# lazurite_rev3.net
KiCad netlist of a schematic drawn in EAGLE
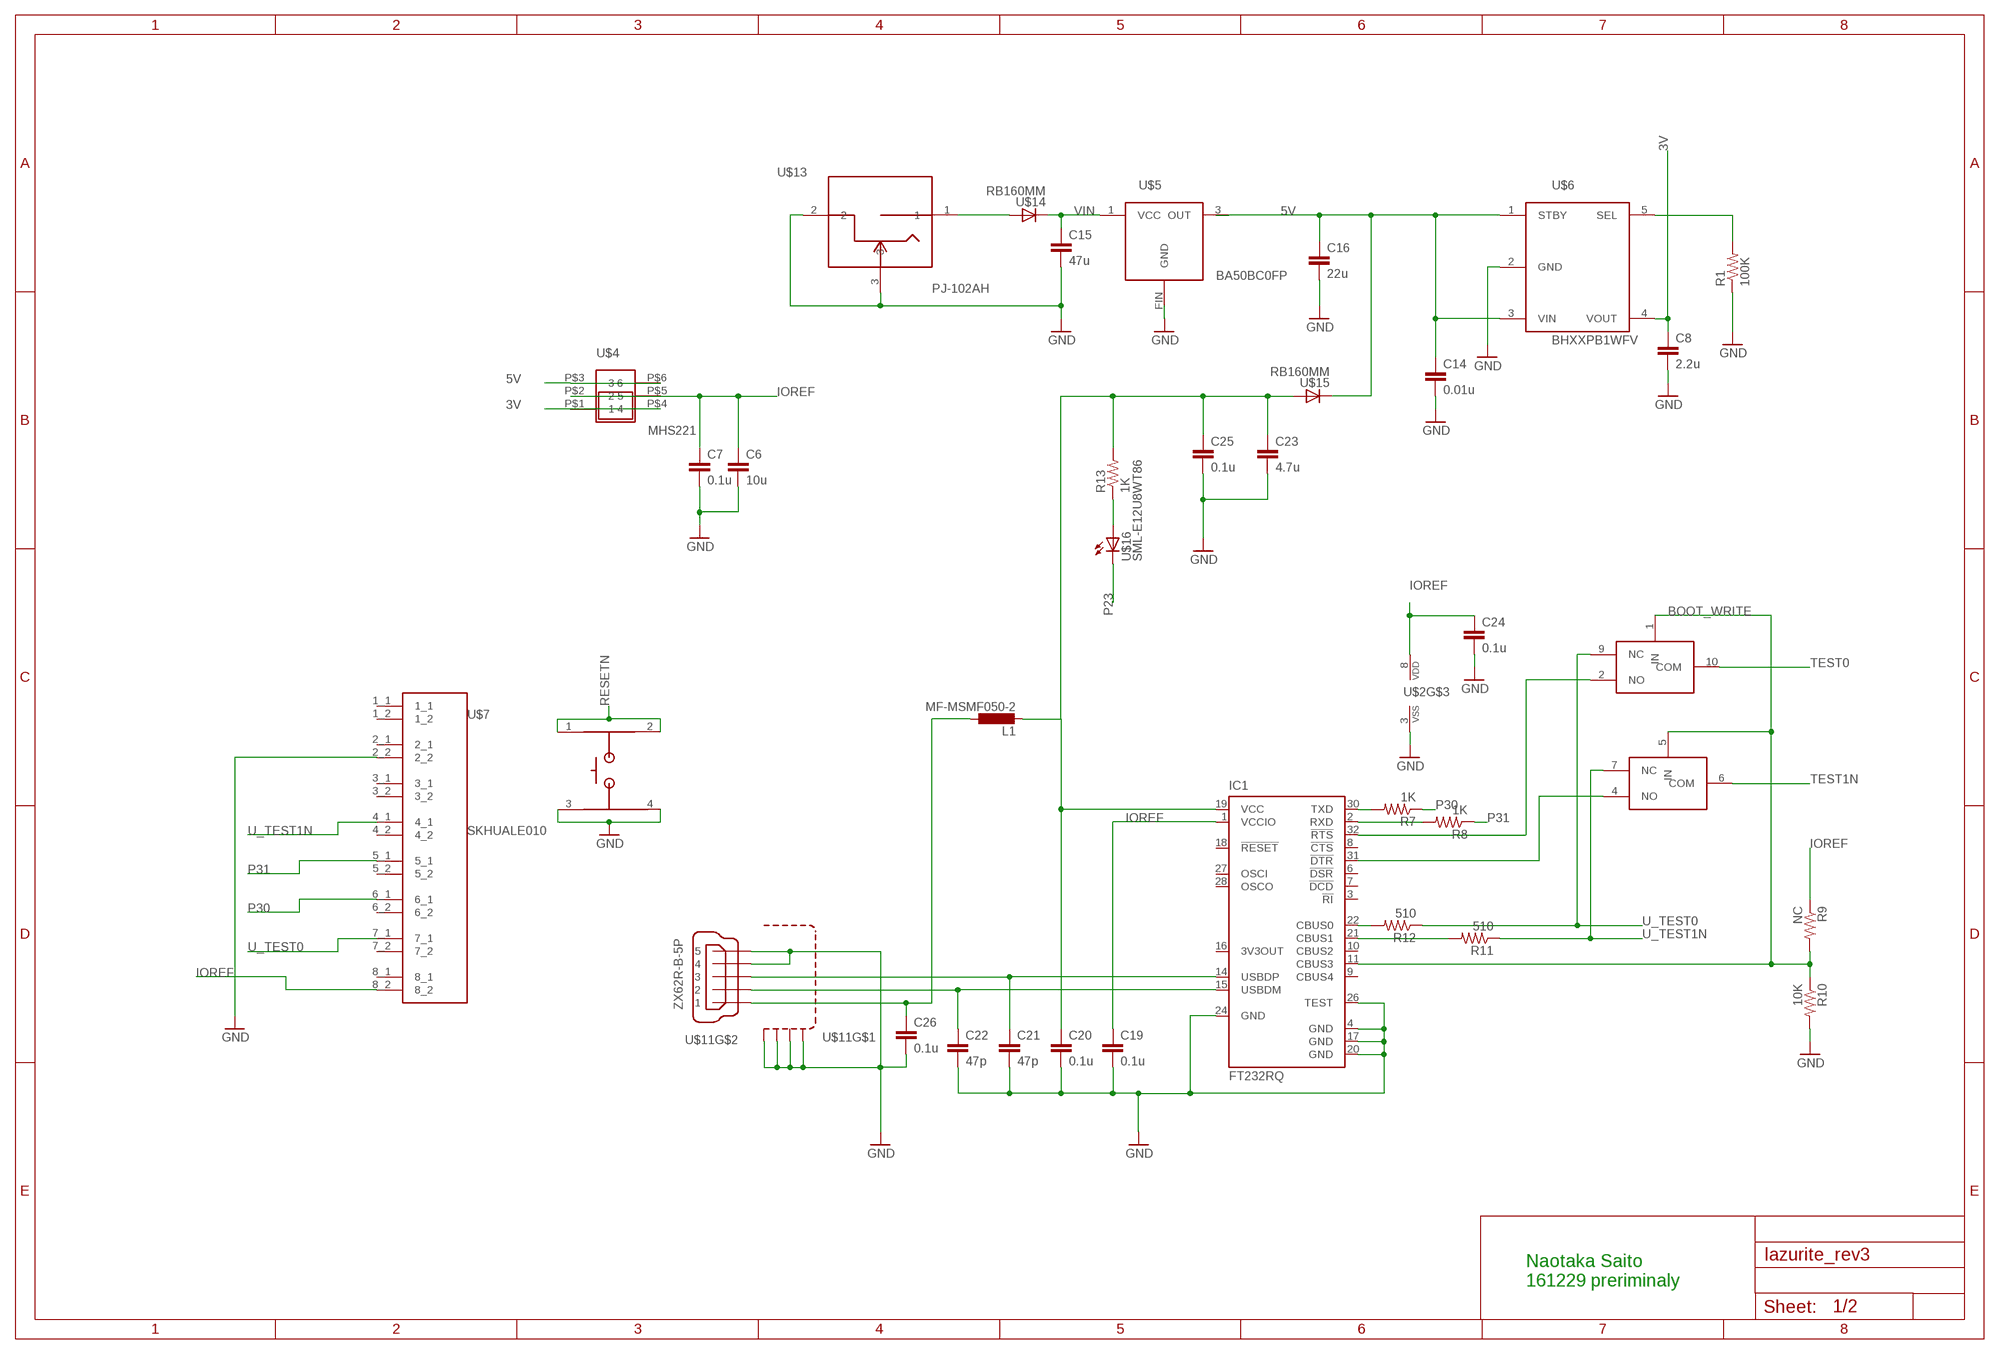
[diagram p0: schematic, sheet 1]
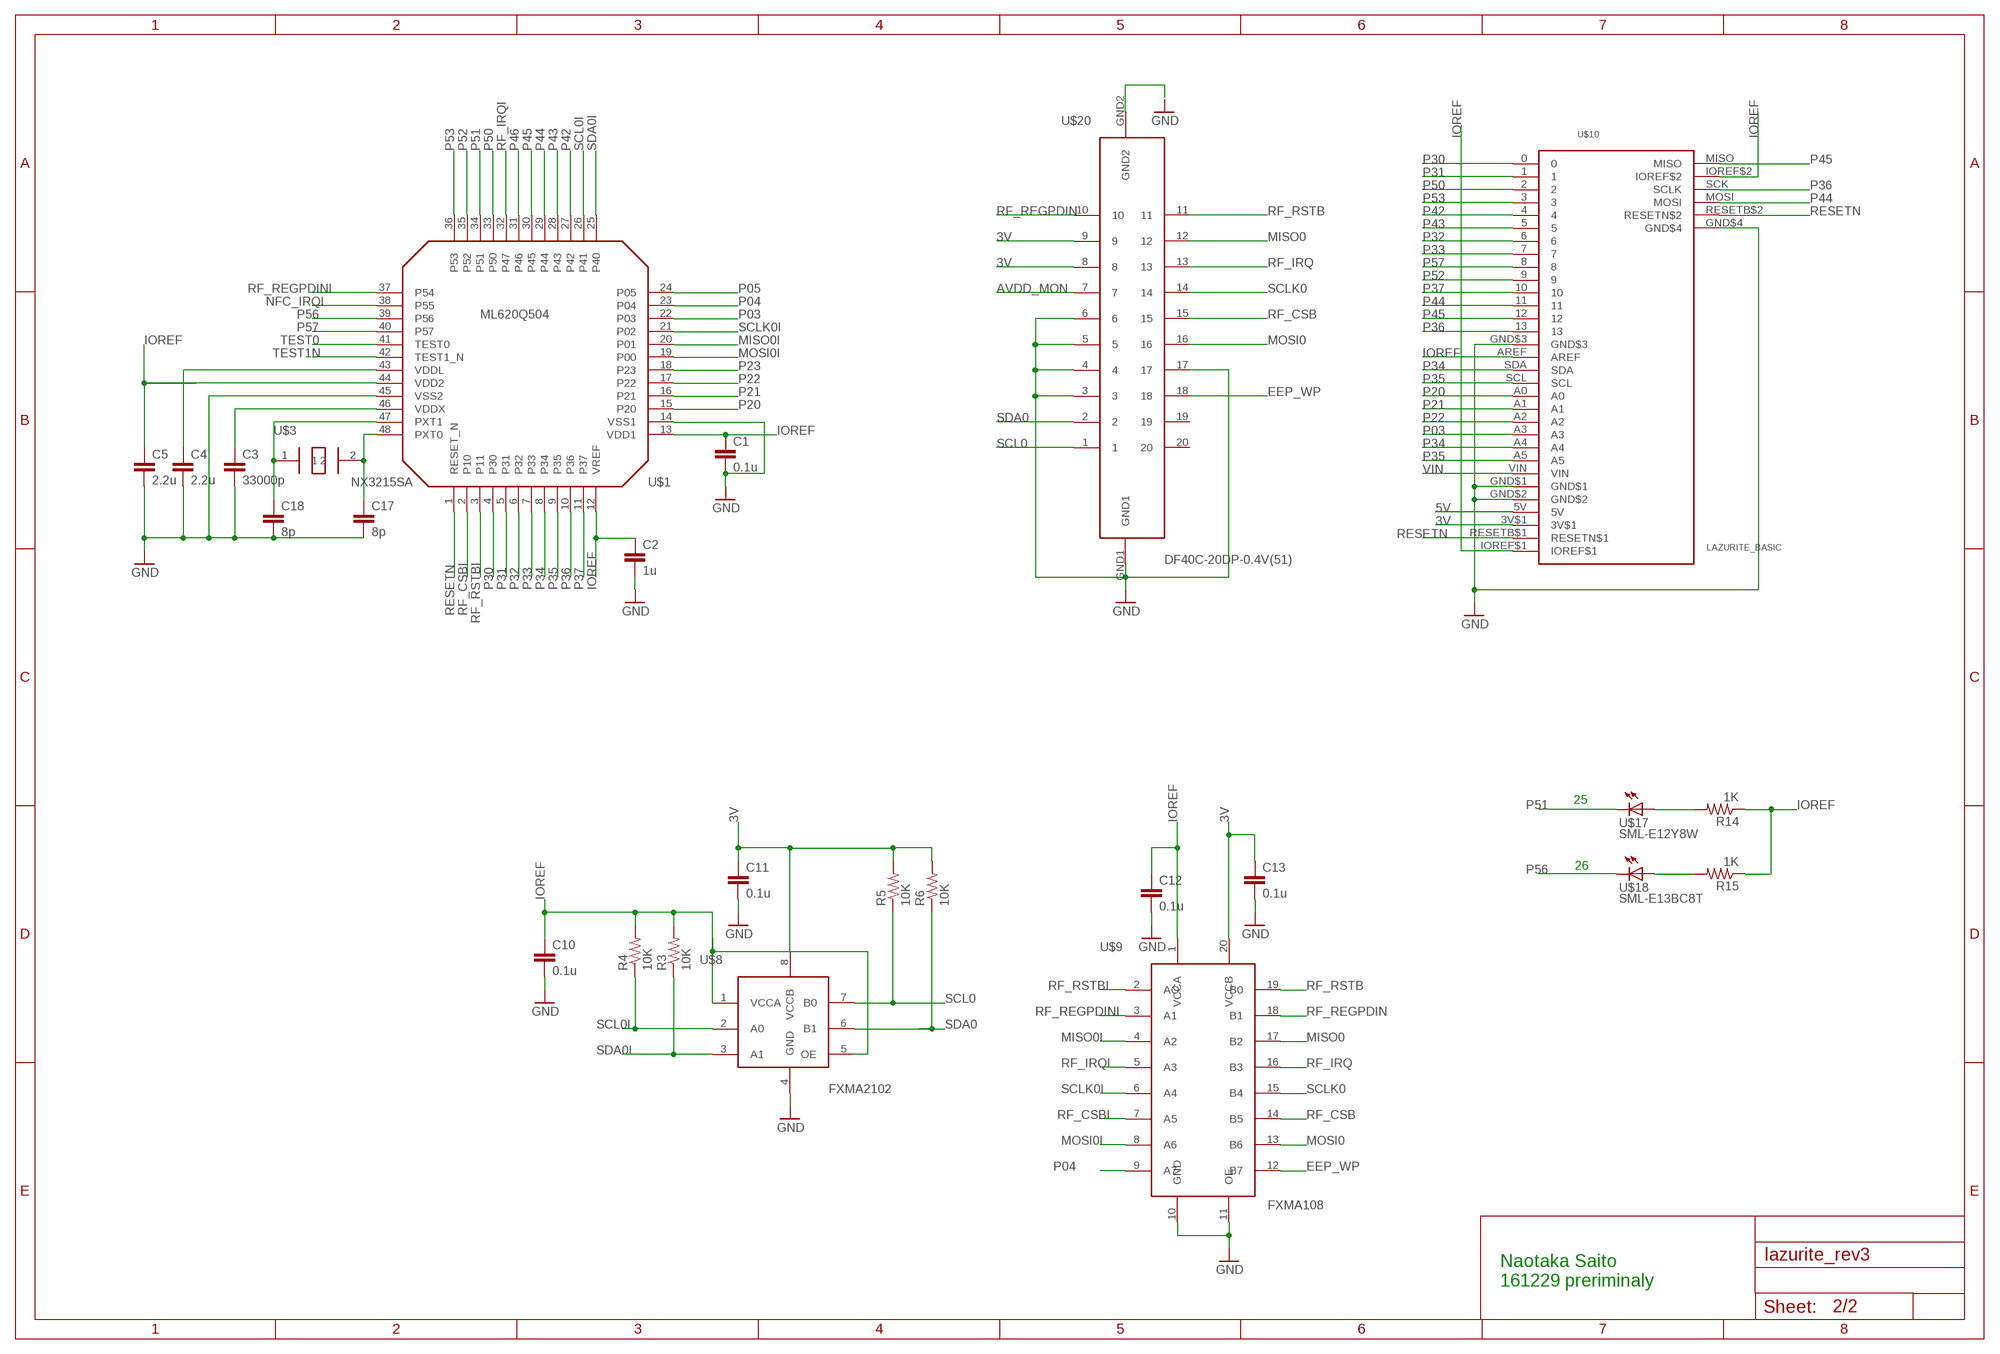
[diagram p1: schematic, sheet 2]

(export (version "E")
  (design (tool "Eeschema 10.0.6"))
  (components
    (comp (ref "C6")
      (value "10u")
      (footprint "eagle-import:C0402")
      (libsource (lib "eagle-import") (part "C-EUC0402"))
    )
    (comp (ref "C7")
      (value "0.1u")
      (footprint "eagle-import:C0402")
      (libsource (lib "eagle-import") (part "C-EUC0402"))
    )
    (comp (ref "C8")
      (value "2.2u")
      (footprint "eagle-import:C0402")
      (libsource (lib "eagle-import") (part "C-EUC0402"))
    )
    (comp (ref "C14")
      (value "0.01u")
      (footprint "eagle-import:C0402")
      (libsource (lib "eagle-import") (part "C-EUC0402"))
    )
    (comp (ref "C15")
      (value "47u")
      (footprint "eagle-import:C1210")
      (libsource (lib "eagle-import") (part "C-EUC1210"))
    )
    (comp (ref "C16")
      (value "22u")
      (footprint "eagle-import:C1206")
      (libsource (lib "eagle-import") (part "C-EUC1206"))
    )
    (comp (ref "C19")
      (value "0.1u")
      (footprint "eagle-import:C0402")
      (libsource (lib "eagle-import") (part "C-EUC0402"))
    )
    (comp (ref "C20")
      (value "0.1u")
      (footprint "eagle-import:C0402")
      (libsource (lib "eagle-import") (part "C-EUC0402"))
    )
    (comp (ref "C21")
      (value "47p")
      (footprint "eagle-import:C0402")
      (libsource (lib "eagle-import") (part "C-EUC0402"))
    )
    (comp (ref "C22")
      (value "47p")
      (footprint "eagle-import:C0402")
      (libsource (lib "eagle-import") (part "C-EUC0402"))
    )
    (comp (ref "C23")
      (value "4.7u")
      (footprint "eagle-import:C0402")
      (libsource (lib "eagle-import") (part "C-EUC0402"))
    )
    (comp (ref "C24")
      (value "0.1u")
      (footprint "eagle-import:C0402")
      (libsource (lib "eagle-import") (part "C-EUC0402"))
    )
    (comp (ref "C25")
      (value "0.1u")
      (footprint "eagle-import:C0402")
      (libsource (lib "eagle-import") (part "C-EUC0402"))
    )
    (comp (ref "C26")
      (value "0.1u")
      (footprint "eagle-import:C0402")
      (libsource (lib "eagle-import") (part "C-EUC0402"))
    )
    (comp (ref "IC1")
      (value "FT232RQ")
      (footprint "eagle-import:QFN32")
      (libsource (lib "eagle-import") (part "FT232RQ"))
    )
    (comp (ref "L1")
      (value "MF-MSMF050-2")
      (footprint "eagle-import:L1812")
      (libsource (lib "eagle-import") (part "L-EUL1812"))
    )
    (comp (ref "R1")
      (value "100K")
      (footprint "eagle-import:R0402")
      (libsource (lib "eagle-import") (part "R-US_R0402"))
    )
    (comp (ref "R7")
      (value "1K")
      (footprint "eagle-import:R0402")
      (libsource (lib "eagle-import") (part "R-US_R0402"))
    )
    (comp (ref "R8")
      (value "1K")
      (footprint "eagle-import:R0402")
      (libsource (lib "eagle-import") (part "R-US_R0402"))
    )
    (comp (ref "R9")
      (value "NC")
      (footprint "eagle-import:R0402")
      (libsource (lib "eagle-import") (part "R-US_R0402"))
    )
    (comp (ref "R10")
      (value "10K")
      (footprint "eagle-import:R0402")
      (libsource (lib "eagle-import") (part "R-US_R0402"))
    )
    (comp (ref "R11")
      (value "510")
      (footprint "eagle-import:R0402")
      (libsource (lib "eagle-import") (part "R-US_R0402"))
    )
    (comp (ref "R12")
      (value "510")
      (footprint "eagle-import:R0402")
      (libsource (lib "eagle-import") (part "R-US_R0402"))
    )
    (comp (ref "R13")
      (value "1K")
      (footprint "eagle-import:R0402")
      (libsource (lib "eagle-import") (part "R-US_R0402"))
    )
    (comp (ref "U$2")
      (value "TI-TS5A23159")
      (footprint "eagle-import:UQFN10")
      (libsource (lib "eagle-import") (part "TI-TS5A23159"))
    )
    (comp (ref "U$4")
      (value "MHS221")
      (footprint "eagle-import:MHS221")
      (libsource (lib "eagle-import") (part "MHS221"))
    )
    (comp (ref "U$5")
      (value "BA50BC0FP")
      (footprint "eagle-import:TO252-3")
      (libsource (lib "eagle-import") (part "BA50BC0FP"))
    )
    (comp (ref "U$6")
      (value "BHXXPB1WFV")
      (footprint "eagle-import:HVSOF5")
      (libsource (lib "eagle-import") (part "BHXXPB1WFV"))
    )
    (comp (ref "U$7")
      (value "SKHUALE010")
      (footprint "eagle-import:SKHUALE010")
      (libsource (lib "eagle-import") (part "SKHUALE010"))
    )
    (comp (ref "U$11")
      (value "ZX62R-B-5P")
      (footprint "eagle-import:ZX62R-B-5P")
      (libsource (lib "eagle-import") (part "MICRO-USB-SHIELD-ZX62R-B-5P"))
    )
    (comp (ref "U$12")
      (value "XB-1-X")
      (footprint "eagle-import:XB-1-X")
      (libsource (lib "eagle-import") (part "XB-1-X"))
    )
    (comp (ref "U$13")
      (value "PJ-102AH")
      (footprint "eagle-import:PJ-102H")
      (libsource (lib "eagle-import") (part "PJ-102AH"))
    )
    (comp (ref "U$14")
      (value "RB160MM")
      (footprint "eagle-import:RB160MM-30")
      (libsource (lib "eagle-import") (part "RB160MM"))
    )
    (comp (ref "U$15")
      (value "RB160MM")
      (footprint "eagle-import:RB160MM-30")
      (libsource (lib "eagle-import") (part "RB160MM"))
    )
    (comp (ref "U$16")
      (value "SML-E12U8WT86")
      (footprint "eagle-import:SML-E1X")
      (libsource (lib "eagle-import") (part "SML-E1X"))
    )
    (comp (ref "C1")
      (value "0.1u")
      (footprint "eagle-import:C0402")
      (libsource (lib "eagle-import") (part "C-EUC0402"))
    )
    (comp (ref "C2")
      (value "1u")
      (footprint "eagle-import:C0402")
      (libsource (lib "eagle-import") (part "C-EUC0402"))
    )
    (comp (ref "C3")
      (value "33000p")
      (footprint "eagle-import:C0402")
      (libsource (lib "eagle-import") (part "C-EUC0402"))
    )
    (comp (ref "C4")
      (value "2.2u")
      (footprint "eagle-import:C0402")
      (libsource (lib "eagle-import") (part "C-EUC0402"))
    )
    (comp (ref "C5")
      (value "2.2u")
      (footprint "eagle-import:C0402")
      (libsource (lib "eagle-import") (part "C-EUC0402"))
    )
    (comp (ref "C10")
      (value "0.1u")
      (footprint "eagle-import:C0402")
      (libsource (lib "eagle-import") (part "C-EUC0402"))
    )
    (comp (ref "C11")
      (value "0.1u")
      (footprint "eagle-import:C0402")
      (libsource (lib "eagle-import") (part "C-EUC0402"))
    )
    (comp (ref "C12")
      (value "0.1u")
      (footprint "eagle-import:C0402")
      (libsource (lib "eagle-import") (part "C-EUC0402"))
    )
    (comp (ref "C13")
      (value "0.1u")
      (footprint "eagle-import:C0402")
      (libsource (lib "eagle-import") (part "C-EUC0402"))
    )
    (comp (ref "C17")
      (value "8p")
      (footprint "eagle-import:C0402")
      (libsource (lib "eagle-import") (part "C-EUC0402"))
    )
    (comp (ref "C18")
      (value "8p")
      (footprint "eagle-import:C0402")
      (libsource (lib "eagle-import") (part "C-EUC0402"))
    )
    (comp (ref "R3")
      (value "10K")
      (footprint "eagle-import:R0402")
      (libsource (lib "eagle-import") (part "R-US_R0402"))
    )
    (comp (ref "R4")
      (value "10K")
      (footprint "eagle-import:R0402")
      (libsource (lib "eagle-import") (part "R-US_R0402"))
    )
    (comp (ref "R5")
      (value "10K")
      (footprint "eagle-import:R0402")
      (libsource (lib "eagle-import") (part "R-US_R0402"))
    )
    (comp (ref "R6")
      (value "10K")
      (footprint "eagle-import:R0402")
      (libsource (lib "eagle-import") (part "R-US_R0402"))
    )
    (comp (ref "R14")
      (value "1K")
      (footprint "eagle-import:R0402")
      (libsource (lib "eagle-import") (part "R-US_R0402"))
    )
    (comp (ref "R15")
      (value "1K")
      (footprint "eagle-import:R0402")
      (libsource (lib "eagle-import") (part "R-US_R0402"))
    )
    (comp (ref "U$1")
      (value "ML620Q504")
      (footprint "eagle-import:ML620Q504")
      (libsource (lib "eagle-import") (part "ML620Q504"))
    )
    (comp (ref "U$3")
      (value "NX3215SA")
      (footprint "eagle-import:NX3215SA-32,768K-SFD-MUA-14")
      (libsource (lib "eagle-import") (part "NX3215SA"))
    )
    (comp (ref "U$8")
      (value "FXMA2102")
      (footprint "eagle-import:MICROPACK")
      (libsource (lib "eagle-import") (part "FXMA2102"))
    )
    (comp (ref "U$9")
      (value "FXMA108")
      (footprint "eagle-import:FXMA108")
      (libsource (lib "eagle-import") (part "FXMA108"))
    )
    (comp (ref "U$10")
      (value "LAZURITE_BASIC")
      (footprint "eagle-import:LAZURITE_BASIC")
      (libsource (lib "eagle-import") (part "LAZURITE_BASIC"))
    )
    (comp (ref "U$17")
      (value "SML-E12Y8W")
      (footprint "eagle-import:SML-E1X")
      (libsource (lib "eagle-import") (part "SML-E1X"))
    )
    (comp (ref "U$18")
      (value "SML-E13BC8T")
      (footprint "eagle-import:SML-E1X")
      (libsource (lib "eagle-import") (part "SML-E1X"))
    )
    (comp (ref "U$20")
      (value "DF40C-20DP-0.4V(51)")
      (footprint "eagle-import:BP3596A")
      (libsource (lib "eagle-import") (part "BP3596A"))
    )
  )
  (nets
    (net (code "1") (name "3V") (class "Default")
      (node (ref "C11") (pin "1") (pinfunction "1_1") (pintype "passive"))
      (node (ref "C13") (pin "1") (pinfunction "1_1") (pintype "passive"))
      (node (ref "C8") (pin "1") (pinfunction "1_1") (pintype "passive"))
      (node (ref "R5") (pin "2") (pinfunction "2_2") (pintype "passive"))
      (node (ref "R6") (pin "2") (pinfunction "2_2") (pintype "passive"))
      (node (ref "U$10") (pin "3V$1") (pinfunction "3V$1_3V$1") (pintype "power_in"))
      (node (ref "U$20") (pin "8") (pinfunction "8_8") (pintype "bidirectional"))
      (node (ref "U$20") (pin "9") (pinfunction "9_9") (pintype "bidirectional"))
      (node (ref "U$4") (pin "P$1") (pinfunction "1_P$1") (pintype "bidirectional"))
      (node (ref "U$4") (pin "P$4") (pinfunction "4_P$4") (pintype "bidirectional"))
      (node (ref "U$6") (pin "4") (pinfunction "VOUT_4") (pintype "bidirectional"))
      (node (ref "U$8") (pin "8") (pinfunction "VCCB_8") (pintype "bidirectional"))
      (node (ref "U$9") (pin "20") (pinfunction "VCCB_20") (pintype "bidirectional"))
    )
    (net (code "2") (name "5V") (class "Default")
      (node (ref "C14") (pin "1") (pinfunction "1_1") (pintype "passive"))
      (node (ref "C16") (pin "1") (pinfunction "1_1") (pintype "passive"))
      (node (ref "U$10") (pin "5V") (pinfunction "5V_5V") (pintype "power_in"))
      (node (ref "U$15") (pin "C") (pinfunction "C_C") (pintype "passive"))
      (node (ref "U$4") (pin "P$3") (pinfunction "3_P$3") (pintype "bidirectional"))
      (node (ref "U$4") (pin "P$6") (pinfunction "6_P$6") (pintype "bidirectional"))
      (node (ref "U$5") (pin "3") (pinfunction "OUT_3") (pintype "bidirectional"))
      (node (ref "U$6") (pin "1") (pinfunction "STBY_1") (pintype "bidirectional"))
      (node (ref "U$6") (pin "3") (pinfunction "VIN_3") (pintype "bidirectional"))
    )
    (net (code "3") (name "AVDD_MON") (class "Default")
      (node (ref "U$20") (pin "7") (pinfunction "7_7") (pintype "bidirectional"))
    )
    (net (code "4") (name "BOOT_WRITE") (class "Default")
      (node (ref "IC1") (pin "11") (pinfunction "CBUS3_11") (pintype "bidirectional"))
      (node (ref "R10") (pin "1") (pinfunction "1_1") (pintype "passive"))
      (node (ref "R9") (pin "2") (pinfunction "2_2") (pintype "passive"))
      (node (ref "U$2") (pin "1") (pinfunction "IN_1") (pintype "bidirectional"))
      (node (ref "U$2") (pin "5") (pinfunction "IN_5") (pintype "bidirectional"))
    )
    (net (code "5") (name "EEP_WP") (class "Default")
      (node (ref "U$20") (pin "18") (pinfunction "18_18") (pintype "bidirectional"))
      (node (ref "U$9") (pin "12") (pinfunction "B7_12") (pintype "bidirectional"))
    )
    (net (code "6") (name "GND") (class "Default")
      (node (ref "C1") (pin "2") (pinfunction "2_2") (pintype "passive"))
      (node (ref "C10") (pin "2") (pinfunction "2_2") (pintype "passive"))
      (node (ref "C11") (pin "2") (pinfunction "2_2") (pintype "passive"))
      (node (ref "C12") (pin "2") (pinfunction "2_2") (pintype "passive"))
      (node (ref "C13") (pin "2") (pinfunction "2_2") (pintype "passive"))
      (node (ref "C14") (pin "2") (pinfunction "2_2") (pintype "passive"))
      (node (ref "C15") (pin "2") (pinfunction "2_2") (pintype "passive"))
      (node (ref "C16") (pin "2") (pinfunction "2_2") (pintype "passive"))
      (node (ref "C17") (pin "2") (pinfunction "2_2") (pintype "passive"))
      (node (ref "C18") (pin "2") (pinfunction "2_2") (pintype "passive"))
      (node (ref "C19") (pin "2") (pinfunction "2_2") (pintype "passive"))
      (node (ref "C2") (pin "2") (pinfunction "2_2") (pintype "passive"))
      (node (ref "C20") (pin "2") (pinfunction "2_2") (pintype "passive"))
      (node (ref "C21") (pin "2") (pinfunction "2_2") (pintype "passive"))
      (node (ref "C22") (pin "2") (pinfunction "2_2") (pintype "passive"))
      (node (ref "C23") (pin "2") (pinfunction "2_2") (pintype "passive"))
      (node (ref "C24") (pin "2") (pinfunction "2_2") (pintype "passive"))
      (node (ref "C25") (pin "2") (pinfunction "2_2") (pintype "passive"))
      (node (ref "C26") (pin "2") (pinfunction "2_2") (pintype "passive"))
      (node (ref "C3") (pin "2") (pinfunction "2_2") (pintype "passive"))
      (node (ref "C4") (pin "2") (pinfunction "2_2") (pintype "passive"))
      (node (ref "C5") (pin "2") (pinfunction "2_2") (pintype "passive"))
      (node (ref "C6") (pin "2") (pinfunction "2_2") (pintype "passive"))
      (node (ref "C7") (pin "2") (pinfunction "2_2") (pintype "passive"))
      (node (ref "C8") (pin "2") (pinfunction "2_2") (pintype "passive"))
      (node (ref "IC1") (pin "17") (pinfunction "GND_17") (pintype "power_in"))
      (node (ref "IC1") (pin "20") (pinfunction "GND_20") (pintype "power_in"))
      (node (ref "IC1") (pin "24") (pinfunction "GND_24") (pintype "power_in"))
      (node (ref "IC1") (pin "26") (pinfunction "TEST_26") (pintype "input"))
      (node (ref "IC1") (pin "4") (pinfunction "GND_4") (pintype "power_in"))
      (node (ref "R1") (pin "1") (pinfunction "1_1") (pintype "passive"))
      (node (ref "R10") (pin "2") (pinfunction "2_2") (pintype "passive"))
      (node (ref "U$1") (pin "14") (pinfunction "VSS1_14") (pintype "bidirectional"))
      (node (ref "U$1") (pin "45") (pinfunction "VSS2_45") (pintype "bidirectional"))
      (node (ref "U$10") (pin "GND$1") (pinfunction "GND$1_GND$1") (pintype "power_in"))
      (node (ref "U$10") (pin "GND$2") (pinfunction "GND$2_GND$2") (pintype "power_in"))
      (node (ref "U$10") (pin "GND$3") (pinfunction "GND$3_GND$3") (pintype "power_in"))
      (node (ref "U$10") (pin "GND$4") (pinfunction "GND$4_GND$4") (pintype "power_in"))
      (node (ref "U$11") (pin "4") (pinfunction "4_4") (pintype "input"))
      (node (ref "U$11") (pin "5") (pinfunction "5_5") (pintype "input"))
      (node (ref "U$11") (pin "M1") (pinfunction "S1_M1") (pintype "passive"))
      (node (ref "U$11") (pin "M2") (pinfunction "S2_M2") (pintype "passive"))
      (node (ref "U$11") (pin "M3") (pinfunction "S3_M3") (pintype "passive"))
      (node (ref "U$11") (pin "M4") (pinfunction "S4_M4") (pintype "passive"))
      (node (ref "U$12") (pin "2_2") (pinfunction "2_2_2_2") (pintype "bidirectional"))
      (node (ref "U$13") (pin "2") (pinfunction "2_2") (pintype "bidirectional"))
      (node (ref "U$13") (pin "3") (pinfunction "3_3") (pintype "bidirectional"))
      (node (ref "U$2") (pin "3") (pinfunction "VSS_3") (pintype "power_in"))
      (node (ref "U$20") (pin "17") (pinfunction "17_17") (pintype "bidirectional"))
      (node (ref "U$20") (pin "3") (pinfunction "3_3") (pintype "bidirectional"))
      (node (ref "U$20") (pin "4") (pinfunction "4_4") (pintype "bidirectional"))
      (node (ref "U$20") (pin "5") (pinfunction "5_5") (pintype "bidirectional"))
      (node (ref "U$20") (pin "6") (pinfunction "6_6") (pintype "bidirectional"))
      (node (ref "U$20") (pin "GND1") (pinfunction "GND1_GND1") (pintype "bidirectional"))
      (node (ref "U$5") (pin "FIN") (pinfunction "GND_FIN") (pintype "bidirectional"))
      (node (ref "U$6") (pin "2") (pinfunction "GND_2") (pintype "bidirectional"))
      (node (ref "U$7") (pin "3") (pinfunction "3_3") (pintype "bidirectional"))
      (node (ref "U$7") (pin "4") (pinfunction "4_4") (pintype "bidirectional"))
      (node (ref "U$8") (pin "4") (pinfunction "GND_4") (pintype "bidirectional"))
      (node (ref "U$9") (pin "10") (pinfunction "GND_10") (pintype "bidirectional"))
      (node (ref "U$9") (pin "11") (pinfunction "OE_11") (pintype "bidirectional"))
    )
    (net (code "7") (name "IOREF") (class "Default")
      (node (ref "C1") (pin "1") (pinfunction "1_1") (pintype "passive"))
      (node (ref "C10") (pin "1") (pinfunction "1_1") (pintype "passive"))
      (node (ref "C12") (pin "1") (pinfunction "1_1") (pintype "passive"))
      (node (ref "C19") (pin "1") (pinfunction "1_1") (pintype "passive"))
      (node (ref "C2") (pin "1") (pinfunction "1_1") (pintype "passive"))
      (node (ref "C24") (pin "1") (pinfunction "1_1") (pintype "passive"))
      (node (ref "C5") (pin "1") (pinfunction "1_1") (pintype "passive"))
      (node (ref "C6") (pin "1") (pinfunction "1_1") (pintype "passive"))
      (node (ref "C7") (pin "1") (pinfunction "1_1") (pintype "passive"))
      (node (ref "IC1") (pin "1") (pinfunction "VCCIO_1") (pintype "power_in"))
      (node (ref "R14") (pin "1") (pinfunction "1_1") (pintype "passive"))
      (node (ref "R15") (pin "1") (pinfunction "1_1") (pintype "passive"))
      (node (ref "R3") (pin "2") (pinfunction "2_2") (pintype "passive"))
      (node (ref "R4") (pin "2") (pinfunction "2_2") (pintype "passive"))
      (node (ref "R9") (pin "1") (pinfunction "1_1") (pintype "passive"))
      (node (ref "U$1") (pin "12") (pinfunction "VREF_12") (pintype "bidirectional"))
      (node (ref "U$1") (pin "13") (pinfunction "VDD1_13") (pintype "bidirectional"))
      (node (ref "U$1") (pin "44") (pinfunction "VDD2_44") (pintype "bidirectional"))
      (node (ref "U$10") (pin "AREF") (pinfunction "AREF_AREF") (pintype "power_in"))
      (node (ref "U$10") (pin "IOREF$1") (pinfunction "IOREF$1_IOREF$1") (pintype "bidirectional"))
      (node (ref "U$10") (pin "IOREF$2") (pinfunction "IOREF$2_IOREF$2") (pintype "power_in"))
      (node (ref "U$12") (pin "8_2") (pinfunction "8_2_8_2") (pintype "bidirectional"))
      (node (ref "U$2") (pin "8") (pinfunction "VDD_8") (pintype "power_in"))
      (node (ref "U$4") (pin "P$2") (pinfunction "2_P$2") (pintype "bidirectional"))
      (node (ref "U$4") (pin "P$5") (pinfunction "5_P$5") (pintype "bidirectional"))
      (node (ref "U$8") (pin "1") (pinfunction "VCCA_1") (pintype "bidirectional"))
      (node (ref "U$8") (pin "5") (pinfunction "OE_5") (pintype "bidirectional"))
      (node (ref "U$9") (pin "1") (pinfunction "VCCA_1") (pintype "bidirectional"))
    )
    (net (code "8") (name "MISO0") (class "Default")
      (node (ref "U$20") (pin "12") (pinfunction "12_12") (pintype "bidirectional"))
      (node (ref "U$9") (pin "17") (pinfunction "B2_17") (pintype "bidirectional"))
    )
    (net (code "9") (name "MISO0I") (class "Default")
      (node (ref "U$1") (pin "20") (pinfunction "P01_20") (pintype "bidirectional"))
      (node (ref "U$9") (pin "4") (pinfunction "A2_4") (pintype "bidirectional"))
    )
    (net (code "10") (name "MOSI0") (class "Default")
      (node (ref "U$20") (pin "16") (pinfunction "16_16") (pintype "bidirectional"))
      (node (ref "U$9") (pin "13") (pinfunction "B6_13") (pintype "bidirectional"))
    )
    (net (code "11") (name "MOSI0I") (class "Default")
      (node (ref "U$1") (pin "19") (pinfunction "P00_19") (pintype "bidirectional"))
      (node (ref "U$9") (pin "8") (pinfunction "A6_8") (pintype "bidirectional"))
    )
    (net (code "12") (name "NFC_IRQI") (class "Default")
      (node (ref "U$1") (pin "38") (pinfunction "P55_38") (pintype "bidirectional"))
    )
    (net (code "13") (name "Net-(C26-Pad1)") (class "Default")
      (node (ref "C26") (pin "1") (pinfunction "1_1") (pintype "passive"))
      (node (ref "L1") (pin "1") (pinfunction "1_1") (pintype "passive"))
      (node (ref "U$11") (pin "1") (pinfunction "1_1") (pintype "input"))
    )
    (net (code "14") (name "Net-(IC1-CBUS0)") (class "Default")
      (node (ref "IC1") (pin "22") (pinfunction "CBUS0_22") (pintype "bidirectional"))
      (node (ref "R12") (pin "2") (pinfunction "2_2") (pintype "passive"))
    )
    (net (code "15") (name "Net-(IC1-CBUS1)") (class "Default")
      (node (ref "IC1") (pin "21") (pinfunction "CBUS1_21") (pintype "bidirectional"))
      (node (ref "R11") (pin "2") (pinfunction "2_2") (pintype "passive"))
    )
    (net (code "16") (name "Net-(IC1-RXD)") (class "Default")
      (node (ref "IC1") (pin "2") (pinfunction "RXD_2") (pintype "input"))
      (node (ref "R8") (pin "2") (pinfunction "2_2") (pintype "passive"))
    )
    (net (code "17") (name "Net-(IC1-TXD)") (class "Default")
      (node (ref "IC1") (pin "30") (pinfunction "TXD_30") (pintype "output"))
      (node (ref "R7") (pin "2") (pinfunction "2_2") (pintype "passive"))
    )
    (net (code "18") (name "Net-(IC1-USBDM)") (class "Default")
      (node (ref "C22") (pin "1") (pinfunction "1_1") (pintype "passive"))
      (node (ref "IC1") (pin "15") (pinfunction "USBDM_15") (pintype "bidirectional"))
      (node (ref "U$11") (pin "2") (pinfunction "2_2") (pintype "input"))
    )
    (net (code "19") (name "Net-(IC1-USBDP)") (class "Default")
      (node (ref "C21") (pin "1") (pinfunction "1_1") (pintype "passive"))
      (node (ref "IC1") (pin "14") (pinfunction "USBDP_14") (pintype "bidirectional"))
      (node (ref "U$11") (pin "3") (pinfunction "3_3") (pintype "input"))
    )
    (net (code "20") (name "Net-(IC1-VCC)") (class "Default")
      (node (ref "C20") (pin "1") (pinfunction "1_1") (pintype "passive"))
      (node (ref "C23") (pin "1") (pinfunction "1_1") (pintype "passive"))
      (node (ref "C25") (pin "1") (pinfunction "1_1") (pintype "passive"))
      (node (ref "IC1") (pin "19") (pinfunction "VCC_19") (pintype "power_in"))
      (node (ref "L1") (pin "2") (pinfunction "2_2") (pintype "passive"))
      (node (ref "R13") (pin "2") (pinfunction "2_2") (pintype "passive"))
      (node (ref "U$15") (pin "A") (pinfunction "A_A") (pintype "passive"))
    )
    (net (code "21") (name "Net-(IC1-~{DTR})") (class "Default")
      (node (ref "IC1") (pin "31") (pinfunction "~{DTR}_31") (pintype "output"))
      (node (ref "U$2") (pin "4") (pinfunction "NO_4") (pintype "bidirectional"))
    )
    (net (code "22") (name "Net-(IC1-~{RTS})") (class "Default")
      (node (ref "IC1") (pin "32") (pinfunction "~{RTS}_32") (pintype "output"))
      (node (ref "U$2") (pin "2") (pinfunction "NO_2") (pintype "bidirectional"))
    )
    (net (code "23") (name "Net-(R13-Pad1)") (class "Default")
      (node (ref "R13") (pin "1") (pinfunction "1_1") (pintype "passive"))
      (node (ref "U$16") (pin "A") (pinfunction "A_A") (pintype "passive"))
    )
    (net (code "24") (name "Net-(R14-Pad2)") (class "Default")
      (node (ref "R14") (pin "2") (pinfunction "2_2") (pintype "passive"))
      (node (ref "U$17") (pin "A") (pinfunction "A_A") (pintype "passive"))
    )
    (net (code "25") (name "Net-(R15-Pad2)") (class "Default")
      (node (ref "R15") (pin "2") (pinfunction "2_2") (pintype "passive"))
      (node (ref "U$18") (pin "A") (pinfunction "A_A") (pintype "passive"))
    )
    (net (code "26") (name "Net-(U$1-PXT0)") (class "Default")
      (node (ref "C17") (pin "1") (pinfunction "1_1") (pintype "passive"))
      (node (ref "U$1") (pin "48") (pinfunction "PXT0_48") (pintype "bidirectional"))
      (node (ref "U$3") (pin "2") (pinfunction "2_2") (pintype "bidirectional"))
    )
    (net (code "27") (name "Net-(U$1-PXT1)") (class "Default")
      (node (ref "C18") (pin "1") (pinfunction "1_1") (pintype "passive"))
      (node (ref "U$1") (pin "47") (pinfunction "PXT1_47") (pintype "bidirectional"))
      (node (ref "U$3") (pin "1") (pinfunction "1_1") (pintype "bidirectional"))
    )
    (net (code "28") (name "Net-(U$1-VDDL)") (class "Default")
      (node (ref "C4") (pin "1") (pinfunction "1_1") (pintype "passive"))
      (node (ref "U$1") (pin "43") (pinfunction "VDDL_43") (pintype "bidirectional"))
    )
    (net (code "29") (name "Net-(U$1-VDDX)") (class "Default")
      (node (ref "C3") (pin "1") (pinfunction "1_1") (pintype "passive"))
      (node (ref "U$1") (pin "46") (pinfunction "VDDX_46") (pintype "bidirectional"))
    )
    (net (code "30") (name "Net-(U$6-SEL)") (class "Default")
      (node (ref "R1") (pin "2") (pinfunction "2_2") (pintype "passive"))
      (node (ref "U$6") (pin "5") (pinfunction "SEL_5") (pintype "bidirectional"))
    )
    (net (code "31") (name "Net-(U$13-Pad1)") (class "Default")
      (node (ref "U$13") (pin "1") (pinfunction "1_1") (pintype "bidirectional"))
      (node (ref "U$14") (pin "A") (pinfunction "A_A") (pintype "passive"))
    )
    (net (code "32") (name "P03") (class "Default")
      (node (ref "U$1") (pin "22") (pinfunction "P03_22") (pintype "bidirectional"))
      (node (ref "U$10") (pin "A3") (pinfunction "A3_A3") (pintype "bidirectional"))
    )
    (net (code "33") (name "P04") (class "Default")
      (node (ref "U$1") (pin "23") (pinfunction "P04_23") (pintype "bidirectional"))
      (node (ref "U$9") (pin "9") (pinfunction "A7_9") (pintype "bidirectional"))
    )
    (net (code "34") (name "P05") (class "Default")
      (node (ref "U$1") (pin "24") (pinfunction "P05_24") (pintype "bidirectional"))
    )
    (net (code "35") (name "P20") (class "Default")
      (node (ref "U$1") (pin "15") (pinfunction "P20_15") (pintype "bidirectional"))
      (node (ref "U$10") (pin "A0") (pinfunction "A0_A0") (pintype "bidirectional"))
    )
    (net (code "36") (name "P21") (class "Default")
      (node (ref "U$1") (pin "16") (pinfunction "P21_16") (pintype "bidirectional"))
      (node (ref "U$10") (pin "A1") (pinfunction "A1_A1") (pintype "bidirectional"))
    )
    (net (code "37") (name "P22") (class "Default")
      (node (ref "U$1") (pin "17") (pinfunction "P22_17") (pintype "bidirectional"))
      (node (ref "U$10") (pin "A2") (pinfunction "A2_A2") (pintype "bidirectional"))
    )
    (net (code "38") (name "P23") (class "Default")
      (node (ref "U$1") (pin "18") (pinfunction "P23_18") (pintype "bidirectional"))
      (node (ref "U$16") (pin "C") (pinfunction "C_C") (pintype "passive"))
    )
    (net (code "39") (name "P30") (class "Default")
      (node (ref "R7") (pin "1") (pinfunction "1_1") (pintype "passive"))
      (node (ref "U$1") (pin "4") (pinfunction "P30_4") (pintype "bidirectional"))
      (node (ref "U$10") (pin "0") (pinfunction "0_0") (pintype "bidirectional"))
      (node (ref "U$12") (pin "6_1") (pinfunction "6_1_6_1") (pintype "bidirectional"))
    )
    (net (code "40") (name "P31") (class "Default")
      (node (ref "R8") (pin "1") (pinfunction "1_1") (pintype "passive"))
      (node (ref "U$1") (pin "5") (pinfunction "P31_5") (pintype "bidirectional"))
      (node (ref "U$10") (pin "1") (pinfunction "1_1") (pintype "bidirectional"))
      (node (ref "U$12") (pin "5_1") (pinfunction "5_1_5_1") (pintype "bidirectional"))
    )
    (net (code "41") (name "P32") (class "Default")
      (node (ref "U$1") (pin "6") (pinfunction "P32_6") (pintype "bidirectional"))
      (node (ref "U$10") (pin "6") (pinfunction "6_6") (pintype "bidirectional"))
    )
    (net (code "42") (name "P33") (class "Default")
      (node (ref "U$1") (pin "7") (pinfunction "P33_7") (pintype "bidirectional"))
      (node (ref "U$10") (pin "7") (pinfunction "7_7") (pintype "bidirectional"))
    )
    (net (code "43") (name "P34") (class "Default")
      (node (ref "U$1") (pin "8") (pinfunction "P34_8") (pintype "bidirectional"))
      (node (ref "U$10") (pin "A4") (pinfunction "A4_A4") (pintype "bidirectional"))
      (node (ref "U$10") (pin "SDA") (pinfunction "SDA_SDA") (pintype "bidirectional"))
    )
    (net (code "44") (name "P35") (class "Default")
      (node (ref "U$1") (pin "9") (pinfunction "P35_9") (pintype "bidirectional"))
      (node (ref "U$10") (pin "A5") (pinfunction "A5_A5") (pintype "bidirectional"))
      (node (ref "U$10") (pin "SCL") (pinfunction "SCL_SCL") (pintype "bidirectional"))
    )
    (net (code "45") (name "P36") (class "Default")
      (node (ref "U$1") (pin "10") (pinfunction "P36_10") (pintype "bidirectional"))
      (node (ref "U$10") (pin "13") (pinfunction "13_13") (pintype "bidirectional"))
      (node (ref "U$10") (pin "SCK") (pinfunction "SCLK_SCK") (pintype "bidirectional"))
    )
    (net (code "46") (name "P37") (class "Default")
      (node (ref "U$1") (pin "11") (pinfunction "P37_11") (pintype "bidirectional"))
      (node (ref "U$10") (pin "10") (pinfunction "10_10") (pintype "bidirectional"))
    )
    (net (code "47") (name "P42") (class "Default")
      (node (ref "U$1") (pin "27") (pinfunction "P42_27") (pintype "bidirectional"))
      (node (ref "U$10") (pin "4") (pinfunction "4_4") (pintype "bidirectional"))
    )
    (net (code "48") (name "P43") (class "Default")
      (node (ref "U$1") (pin "28") (pinfunction "P43_28") (pintype "bidirectional"))
      (node (ref "U$10") (pin "5") (pinfunction "5_5") (pintype "bidirectional"))
    )
    (net (code "49") (name "P44") (class "Default")
      (node (ref "U$1") (pin "29") (pinfunction "P44_29") (pintype "bidirectional"))
      (node (ref "U$10") (pin "11") (pinfunction "11_11") (pintype "bidirectional"))
      (node (ref "U$10") (pin "MOSI") (pinfunction "MOSI_MOSI") (pintype "bidirectional"))
    )
    (net (code "50") (name "P45") (class "Default")
      (node (ref "U$1") (pin "30") (pinfunction "P45_30") (pintype "bidirectional"))
      (node (ref "U$10") (pin "12") (pinfunction "12_12") (pintype "bidirectional"))
      (node (ref "U$10") (pin "MISO") (pinfunction "MISO_MISO") (pintype "bidirectional"))
    )
    (net (code "51") (name "P46") (class "Default")
      (node (ref "U$1") (pin "31") (pinfunction "P46_31") (pintype "bidirectional"))
    )
    (net (code "52") (name "P50") (class "Default")
      (node (ref "U$1") (pin "33") (pinfunction "P50_33") (pintype "bidirectional"))
      (node (ref "U$10") (pin "2") (pinfunction "2_2") (pintype "bidirectional"))
    )
    (net (code "53") (name "P51") (class "Default")
      (node (ref "U$1") (pin "34") (pinfunction "P51_34") (pintype "bidirectional"))
      (node (ref "U$17") (pin "C") (pinfunction "C_C") (pintype "passive"))
    )
    (net (code "54") (name "P52") (class "Default")
      (node (ref "U$1") (pin "35") (pinfunction "P52_35") (pintype "bidirectional"))
      (node (ref "U$10") (pin "9") (pinfunction "9_9") (pintype "bidirectional"))
    )
    (net (code "55") (name "P53") (class "Default")
      (node (ref "U$1") (pin "36") (pinfunction "P53_36") (pintype "bidirectional"))
      (node (ref "U$10") (pin "3") (pinfunction "3_3") (pintype "bidirectional"))
    )
    (net (code "56") (name "P56") (class "Default")
      (node (ref "U$1") (pin "39") (pinfunction "P56_39") (pintype "bidirectional"))
      (node (ref "U$18") (pin "C") (pinfunction "C_C") (pintype "passive"))
    )
    (net (code "57") (name "P57") (class "Default")
      (node (ref "U$1") (pin "40") (pinfunction "P57_40") (pintype "bidirectional"))
      (node (ref "U$10") (pin "8") (pinfunction "8_8") (pintype "bidirectional"))
    )
    (net (code "58") (name "RESETN") (class "Default")
      (node (ref "U$1") (pin "1") (pinfunction "RESET_N_1") (pintype "bidirectional"))
      (node (ref "U$10") (pin "RESETB$1") (pinfunction "RESETN$1_RESETB$1") (pintype "bidirectional"))
      (node (ref "U$10") (pin "RESETB$2") (pinfunction "RESETN$2_RESETB$2") (pintype "bidirectional"))
      (node (ref "U$7") (pin "1") (pinfunction "1_1") (pintype "bidirectional"))
      (node (ref "U$7") (pin "2") (pinfunction "2_2") (pintype "bidirectional"))
    )
    (net (code "59") (name "RF_CSB") (class "Default")
      (node (ref "U$20") (pin "15") (pinfunction "15_15") (pintype "bidirectional"))
      (node (ref "U$9") (pin "14") (pinfunction "B5_14") (pintype "bidirectional"))
    )
    (net (code "60") (name "RF_CSBI") (class "Default")
      (node (ref "U$1") (pin "2") (pinfunction "P10_2") (pintype "bidirectional"))
      (node (ref "U$9") (pin "7") (pinfunction "A5_7") (pintype "bidirectional"))
    )
    (net (code "61") (name "RF_IRQ") (class "Default")
      (node (ref "U$20") (pin "13") (pinfunction "13_13") (pintype "bidirectional"))
      (node (ref "U$9") (pin "16") (pinfunction "B3_16") (pintype "bidirectional"))
    )
    (net (code "62") (name "RF_IRQI") (class "Default")
      (node (ref "U$1") (pin "32") (pinfunction "P47_32") (pintype "bidirectional"))
      (node (ref "U$9") (pin "5") (pinfunction "A3_5") (pintype "bidirectional"))
    )
    (net (code "63") (name "RF_REGPDIN") (class "Default")
      (node (ref "U$20") (pin "10") (pinfunction "10_10") (pintype "bidirectional"))
      (node (ref "U$9") (pin "18") (pinfunction "B1_18") (pintype "bidirectional"))
    )
    (net (code "64") (name "RF_REGPDINI") (class "Default")
      (node (ref "U$1") (pin "37") (pinfunction "P54_37") (pintype "bidirectional"))
      (node (ref "U$9") (pin "3") (pinfunction "A1_3") (pintype "bidirectional"))
    )
    (net (code "65") (name "RF_RSTB") (class "Default")
      (node (ref "U$20") (pin "11") (pinfunction "11_11") (pintype "bidirectional"))
      (node (ref "U$9") (pin "19") (pinfunction "B0_19") (pintype "bidirectional"))
    )
    (net (code "66") (name "RF_RSTBI") (class "Default")
      (node (ref "U$1") (pin "3") (pinfunction "P11_3") (pintype "bidirectional"))
      (node (ref "U$9") (pin "2") (pinfunction "AO_2") (pintype "bidirectional"))
    )
    (net (code "67") (name "SCL0") (class "Default")
      (node (ref "R5") (pin "1") (pinfunction "1_1") (pintype "passive"))
      (node (ref "U$20") (pin "1") (pinfunction "1_1") (pintype "bidirectional"))
      (node (ref "U$8") (pin "7") (pinfunction "B0_7") (pintype "bidirectional"))
    )
    (net (code "68") (name "SCL0I") (class "Default")
      (node (ref "R4") (pin "1") (pinfunction "1_1") (pintype "passive"))
      (node (ref "U$1") (pin "26") (pinfunction "P41_26") (pintype "bidirectional"))
      (node (ref "U$8") (pin "2") (pinfunction "A0_2") (pintype "bidirectional"))
    )
    (net (code "69") (name "SCLK0") (class "Default")
      (node (ref "U$20") (pin "14") (pinfunction "14_14") (pintype "bidirectional"))
      (node (ref "U$9") (pin "15") (pinfunction "B4_15") (pintype "bidirectional"))
    )
    (net (code "70") (name "SCLK0I") (class "Default")
      (node (ref "U$1") (pin "21") (pinfunction "P02_21") (pintype "bidirectional"))
      (node (ref "U$9") (pin "6") (pinfunction "A4_6") (pintype "bidirectional"))
    )
    (net (code "71") (name "SDA0") (class "Default")
      (node (ref "R6") (pin "1") (pinfunction "1_1") (pintype "passive"))
      (node (ref "U$20") (pin "2") (pinfunction "2_2") (pintype "bidirectional"))
      (node (ref "U$8") (pin "6") (pinfunction "B1_6") (pintype "bidirectional"))
    )
    (net (code "72") (name "SDA0I") (class "Default")
      (node (ref "R3") (pin "1") (pinfunction "1_1") (pintype "passive"))
      (node (ref "U$1") (pin "25") (pinfunction "P40_25") (pintype "bidirectional"))
      (node (ref "U$8") (pin "3") (pinfunction "A1_3") (pintype "bidirectional"))
    )
    (net (code "73") (name "TEST0") (class "Default")
      (node (ref "U$1") (pin "41") (pinfunction "TEST0_41") (pintype "bidirectional"))
      (node (ref "U$2") (pin "10") (pinfunction "COM_10") (pintype "bidirectional"))
    )
    (net (code "74") (name "TEST1N") (class "Default")
      (node (ref "U$1") (pin "42") (pinfunction "TEST1_N_42") (pintype "bidirectional"))
      (node (ref "U$2") (pin "6") (pinfunction "COM_6") (pintype "bidirectional"))
    )
    (net (code "75") (name "U_TEST0") (class "Default")
      (node (ref "R12") (pin "1") (pinfunction "1_1") (pintype "passive"))
      (node (ref "U$12") (pin "7_1") (pinfunction "7_1_7_1") (pintype "bidirectional"))
      (node (ref "U$2") (pin "9") (pinfunction "NC_9") (pintype "bidirectional"))
    )
    (net (code "76") (name "U_TEST1N") (class "Default")
      (node (ref "R11") (pin "1") (pinfunction "1_1") (pintype "passive"))
      (node (ref "U$12") (pin "4_1") (pinfunction "4_1_4_1") (pintype "bidirectional"))
      (node (ref "U$2") (pin "7") (pinfunction "NC_7") (pintype "bidirectional"))
    )
    (net (code "77") (name "VIN") (class "Default")
      (node (ref "C15") (pin "1") (pinfunction "1_1") (pintype "passive"))
      (node (ref "U$10") (pin "VIN") (pinfunction "VIN_VIN") (pintype "power_in"))
      (node (ref "U$14") (pin "C") (pinfunction "C_C") (pintype "passive"))
      (node (ref "U$5") (pin "1") (pinfunction "VCC_1") (pintype "bidirectional"))
    )
    (net (code "78") (name "unconnected-(IC1-3V3OUT-Pad16)") (class "Default")
      (node (ref "IC1") (pin "16") (pinfunction "3V3OUT_16") (pintype "output"))
    )
    (net (code "79") (name "unconnected-(IC1-CBUS2-Pad10)") (class "Default")
      (node (ref "IC1") (pin "10") (pinfunction "CBUS2_10") (pintype "bidirectional"))
    )
    (net (code "80") (name "unconnected-(IC1-CBUS4-Pad9)") (class "Default")
      (node (ref "IC1") (pin "9") (pinfunction "CBUS4_9") (pintype "bidirectional"))
    )
    (net (code "81") (name "unconnected-(IC1-OSCI-Pad27)") (class "Default")
      (node (ref "IC1") (pin "27") (pinfunction "OSCI_27") (pintype "input"))
    )
    (net (code "82") (name "unconnected-(IC1-OSCO-Pad28)") (class "Default")
      (node (ref "IC1") (pin "28") (pinfunction "OSCO_28") (pintype "output"))
    )
    (net (code "83") (name "unconnected-(IC1-~{CTS}-Pad8)") (class "Default")
      (node (ref "IC1") (pin "8") (pinfunction "~{CTS}_8") (pintype "input"))
    )
    (net (code "84") (name "unconnected-(IC1-~{DCD}-Pad7)") (class "Default")
      (node (ref "IC1") (pin "7") (pinfunction "~{DCD}_7") (pintype "input"))
    )
    (net (code "85") (name "unconnected-(IC1-~{DSR}-Pad6)") (class "Default")
      (node (ref "IC1") (pin "6") (pinfunction "~{DSR}_6") (pintype "input"))
    )
    (net (code "86") (name "unconnected-(IC1-~{RESET}-Pad18)") (class "Default")
      (node (ref "IC1") (pin "18") (pinfunction "~{RESET}_18") (pintype "input"))
    )
    (net (code "87") (name "unconnected-(IC1-~{RI}-Pad3)") (class "Default")
      (node (ref "IC1") (pin "3") (pinfunction "~{RI}_3") (pintype "input"))
    )
    (net (code "88") (name "unconnected-(U$12-Pad1_1)") (class "Default")
      (node (ref "U$12") (pin "1_1") (pinfunction "1_1_1_1") (pintype "bidirectional"))
    )
    (net (code "89") (name "unconnected-(U$12-Pad1_2)") (class "Default")
      (node (ref "U$12") (pin "1_2") (pinfunction "1_2_1_2") (pintype "bidirectional"))
    )
    (net (code "90") (name "unconnected-(U$12-Pad2_1)") (class "Default")
      (node (ref "U$12") (pin "2_1") (pinfunction "2_1_2_1") (pintype "bidirectional"))
    )
    (net (code "91") (name "unconnected-(U$12-Pad3_1)") (class "Default")
      (node (ref "U$12") (pin "3_1") (pinfunction "3_1_3_1") (pintype "bidirectional"))
    )
    (net (code "92") (name "unconnected-(U$12-Pad3_2)") (class "Default")
      (node (ref "U$12") (pin "3_2") (pinfunction "3_2_3_2") (pintype "bidirectional"))
    )
    (net (code "93") (name "unconnected-(U$12-Pad4_2)") (class "Default")
      (node (ref "U$12") (pin "4_2") (pinfunction "4_2_4_2") (pintype "bidirectional"))
    )
    (net (code "94") (name "unconnected-(U$12-Pad5_2)") (class "Default")
      (node (ref "U$12") (pin "5_2") (pinfunction "5_2_5_2") (pintype "bidirectional"))
    )
    (net (code "95") (name "unconnected-(U$12-Pad6_2)") (class "Default")
      (node (ref "U$12") (pin "6_2") (pinfunction "6_2_6_2") (pintype "bidirectional"))
    )
    (net (code "96") (name "unconnected-(U$12-Pad7_2)") (class "Default")
      (node (ref "U$12") (pin "7_2") (pinfunction "7_2_7_2") (pintype "bidirectional"))
    )
    (net (code "97") (name "unconnected-(U$12-Pad8_1)") (class "Default")
      (node (ref "U$12") (pin "8_1") (pinfunction "8_1_8_1") (pintype "bidirectional"))
    )
    (net (code "98") (name "unconnected-(U$20-Pad19)") (class "Default")
      (node (ref "U$20") (pin "19") (pinfunction "19_19") (pintype "bidirectional"))
    )
    (net (code "99") (name "unconnected-(U$20-Pad20)") (class "Default")
      (node (ref "U$20") (pin "20") (pinfunction "20_20") (pintype "bidirectional"))
    )
    (net (code "100") (name "unconnected-(U$20-PadGND2)") (class "Default")
      (node (ref "U$20") (pin "GND2") (pinfunction "GND2_GND2") (pintype "bidirectional"))
    )
  )
)
